# schemat2.net
KiCad netlist of a schematic drawn in EAGLE
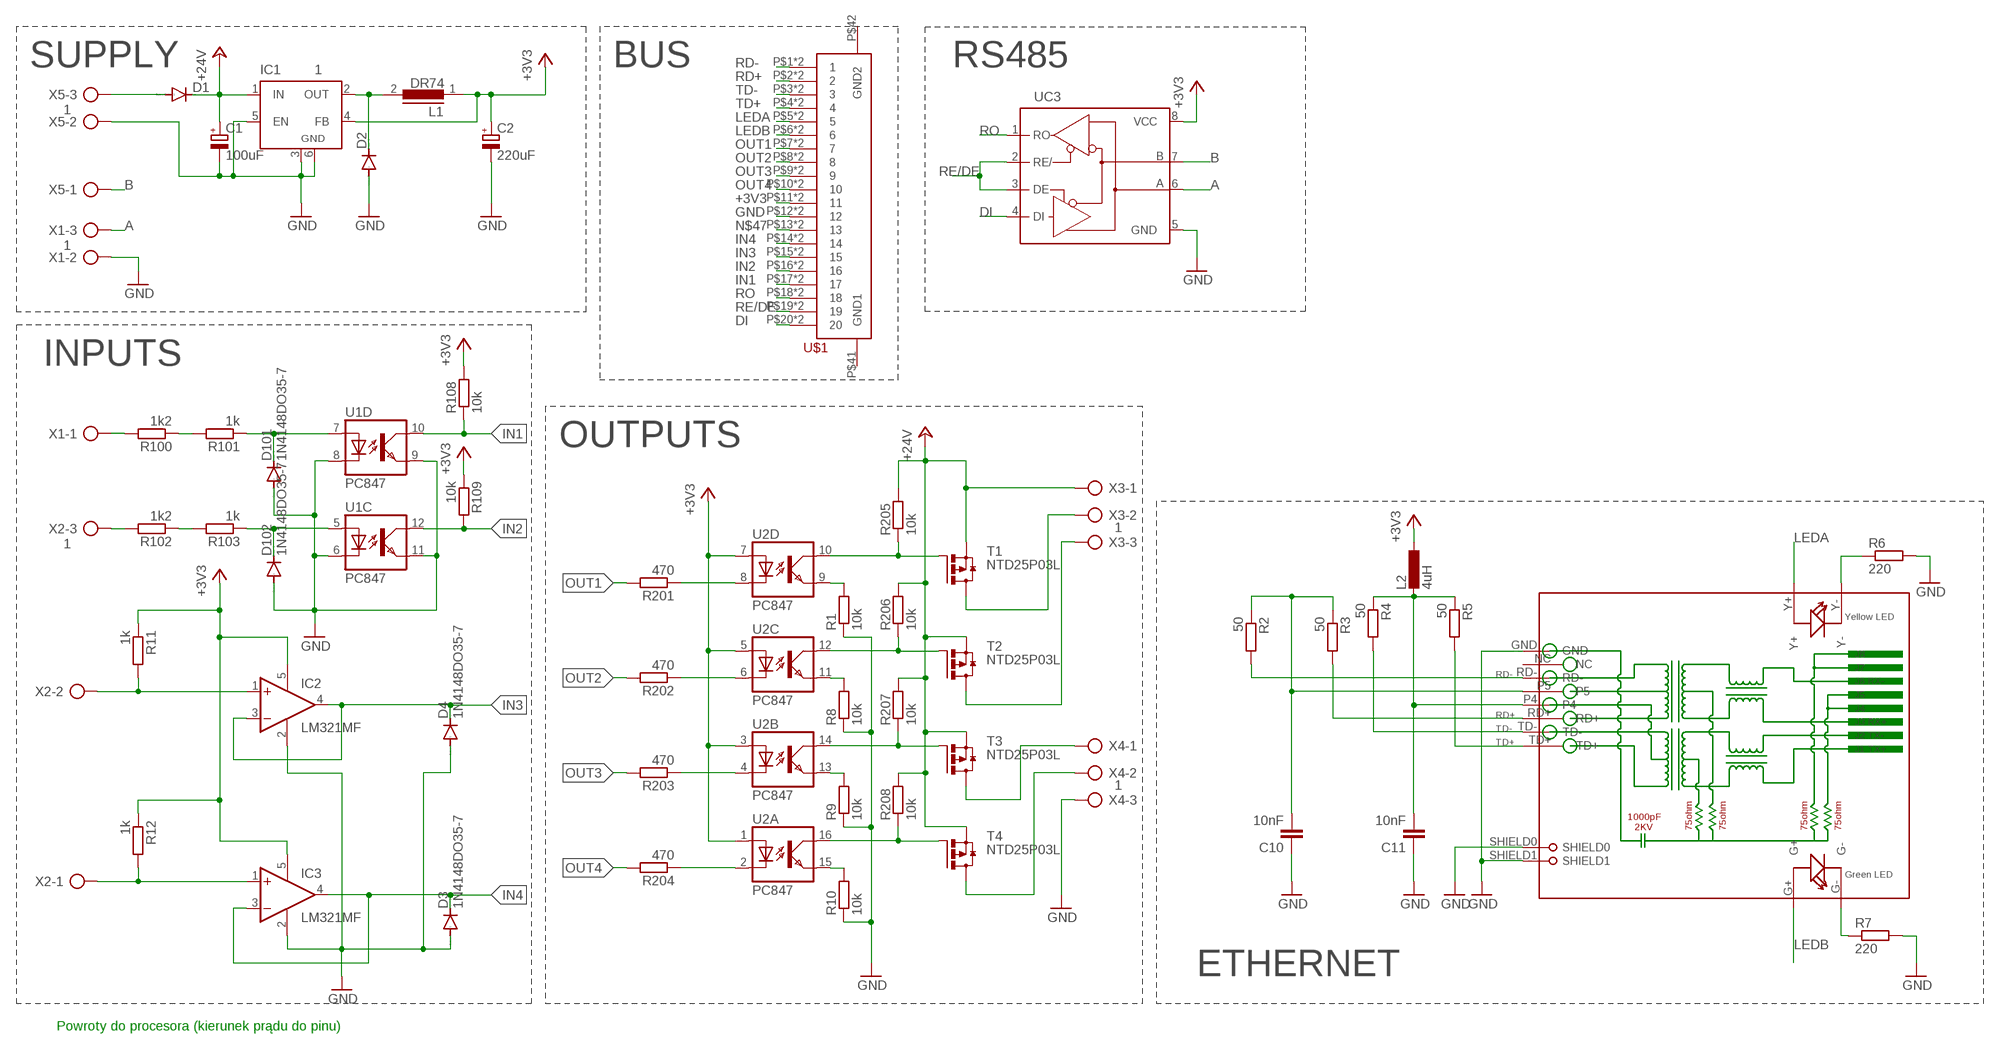
[diagram p0: schematic, sheet 1]

(export (version "E")
  (design (tool "Eeschema 10.0.6"))
  (components
    (comp (ref "C1")
      (value "100uF")
      (footprint "eagle-import:SANYO-OSCON_SMD_E7")
      (libsource (lib "eagle-import") (part "CPOL-EUSANYO_SMD_E7"))
    )
    (comp (ref "C2")
      (value "220uF")
      (footprint "eagle-import:SANYO-OSCON_SMD_E7")
      (libsource (lib "eagle-import") (part "CPOL-EUSANYO_SMD_E7"))
    )
    (comp (ref "C10")
      (value "10nF")
      (footprint "eagle-import:C0805")
      (libsource (lib "eagle-import") (part "C-0805"))
    )
    (comp (ref "C11")
      (value "10nF")
      (footprint "eagle-import:C0805")
      (libsource (lib "eagle-import") (part "C-0805"))
    )
    (comp (ref "D1")
      (value "S1M")
      (footprint "eagle-import:SMA")
      (libsource (lib "eagle-import") (part "S1M"))
    )
    (comp (ref "D2")
      (value "S1M")
      (footprint "eagle-import:SMA")
      (libsource (lib "eagle-import") (part "S1M"))
    )
    (comp (ref "D3")
      (value "1N4148DO35-7")
      (footprint "eagle-import:DO35-7")
      (libsource (lib "eagle-import") (part "1N4148DO35-7"))
    )
    (comp (ref "D4")
      (value "1N4148DO35-7")
      (footprint "eagle-import:DO35-7")
      (libsource (lib "eagle-import") (part "1N4148DO35-7"))
    )
    (comp (ref "D101")
      (value "1N4148DO35-7")
      (footprint "eagle-import:DO35-7")
      (libsource (lib "eagle-import") (part "1N4148DO35-7"))
    )
    (comp (ref "D102")
      (value "1N4148DO35-7")
      (footprint "eagle-import:DO35-7")
      (libsource (lib "eagle-import") (part "1N4148DO35-7"))
    )
    (comp (ref "IC1")
      (value "1")
      (footprint "eagle-import:TO263-5")
      (libsource (lib "eagle-import") (part "LM2596S"))
    )
    (comp (ref "IC2")
      (value "LM321MF")
      (footprint "eagle-import:SOT23-5")
      (libsource (lib "eagle-import") (part "LM321?MF"))
    )
    (comp (ref "IC3")
      (value "LM321MF")
      (footprint "eagle-import:SOT23-5")
      (libsource (lib "eagle-import") (part "LM321?MF"))
    )
    (comp (ref "L1")
      (value "DR74")
      (footprint "eagle-import:DR74")
      (libsource (lib "eagle-import") (part "DR74"))
    )
    (comp (ref "L2")
      (value "4uH")
      (footprint "eagle-import:L2012C")
      (libsource (lib "eagle-import") (part "L-EUL2012C"))
    )
    (comp (ref "R1")
      (value "10k")
      (footprint "eagle-import:R0805W")
      (libsource (lib "eagle-import") (part "R-0805W"))
    )
    (comp (ref "R2")
      (value "50")
      (footprint "eagle-import:R0805")
      (libsource (lib "eagle-import") (part "R-0805"))
    )
    (comp (ref "R3")
      (value "50")
      (footprint "eagle-import:R0805")
      (libsource (lib "eagle-import") (part "R-0805"))
    )
    (comp (ref "R4")
      (value "50")
      (footprint "eagle-import:R0805")
      (libsource (lib "eagle-import") (part "R-0805"))
    )
    (comp (ref "R5")
      (value "50")
      (footprint "eagle-import:R0805")
      (libsource (lib "eagle-import") (part "R-0805"))
    )
    (comp (ref "R6")
      (value "220")
      (footprint "eagle-import:R0805")
      (libsource (lib "eagle-import") (part "R-0805"))
    )
    (comp (ref "R7")
      (value "220")
      (footprint "eagle-import:R0805")
      (libsource (lib "eagle-import") (part "R-0805"))
    )
    (comp (ref "R8")
      (value "10k")
      (footprint "eagle-import:R0805W")
      (libsource (lib "eagle-import") (part "R-0805W"))
    )
    (comp (ref "R9")
      (value "10k")
      (footprint "eagle-import:R0805W")
      (libsource (lib "eagle-import") (part "R-0805W"))
    )
    (comp (ref "R10")
      (value "10k")
      (footprint "eagle-import:R0805W")
      (libsource (lib "eagle-import") (part "R-0805W"))
    )
    (comp (ref "R11")
      (value "1k")
      (footprint "eagle-import:R0805")
      (libsource (lib "eagle-import") (part "R-0805"))
    )
    (comp (ref "R12")
      (value "1k")
      (footprint "eagle-import:R0805")
      (libsource (lib "eagle-import") (part "R-0805"))
    )
    (comp (ref "R100")
      (value "1k2")
      (footprint "eagle-import:R0805")
      (libsource (lib "eagle-import") (part "R-0805"))
    )
    (comp (ref "R101")
      (value "1k")
      (footprint "eagle-import:R0805")
      (libsource (lib "eagle-import") (part "R-0805"))
    )
    (comp (ref "R102")
      (value "1k2")
      (footprint "eagle-import:R0805")
      (libsource (lib "eagle-import") (part "R-0805"))
    )
    (comp (ref "R103")
      (value "1k")
      (footprint "eagle-import:R0805")
      (libsource (lib "eagle-import") (part "R-0805"))
    )
    (comp (ref "R108")
      (value "10k")
      (footprint "eagle-import:R0805")
      (libsource (lib "eagle-import") (part "R-0805"))
    )
    (comp (ref "R109")
      (value "10k")
      (footprint "eagle-import:R0805")
      (libsource (lib "eagle-import") (part "R-0805"))
    )
    (comp (ref "R201")
      (value "470")
      (footprint "eagle-import:R0805")
      (libsource (lib "eagle-import") (part "R-0805"))
    )
    (comp (ref "R202")
      (value "470")
      (footprint "eagle-import:R0805")
      (libsource (lib "eagle-import") (part "R-0805"))
    )
    (comp (ref "R203")
      (value "470")
      (footprint "eagle-import:R0805")
      (libsource (lib "eagle-import") (part "R-0805"))
    )
    (comp (ref "R204")
      (value "470")
      (footprint "eagle-import:R0805")
      (libsource (lib "eagle-import") (part "R-0805"))
    )
    (comp (ref "R205")
      (value "10k")
      (footprint "eagle-import:R0805W")
      (libsource (lib "eagle-import") (part "R-0805W"))
    )
    (comp (ref "R206")
      (value "10k")
      (footprint "eagle-import:R0805W")
      (libsource (lib "eagle-import") (part "R-0805W"))
    )
    (comp (ref "R207")
      (value "10k")
      (footprint "eagle-import:R0805W")
      (libsource (lib "eagle-import") (part "R-0805W"))
    )
    (comp (ref "R208")
      (value "10k")
      (footprint "eagle-import:R0805W")
      (libsource (lib "eagle-import") (part "R-0805W"))
    )
    (comp (ref "RJ1")
      (value "HR911105A")
      (footprint "eagle-import:HR911105A")
      (libsource (lib "eagle-import") (part "HR911105A"))
    )
    (comp (ref "T1")
      (value "NTD25P03L")
      (footprint "eagle-import:DPACK")
      (libsource (lib "eagle-import") (part "NTD25P03L"))
    )
    (comp (ref "T2")
      (value "NTD25P03L")
      (footprint "eagle-import:DPACK")
      (libsource (lib "eagle-import") (part "NTD25P03L"))
    )
    (comp (ref "T3")
      (value "NTD25P03L")
      (footprint "eagle-import:DPACK")
      (libsource (lib "eagle-import") (part "NTD25P03L"))
    )
    (comp (ref "T4")
      (value "NTD25P03L")
      (footprint "eagle-import:DPACK")
      (libsource (lib "eagle-import") (part "NTD25P03L"))
    )
    (comp (ref "U$1")
      (value "FFC(FPC)_ZIF_20_PINV")
      (footprint "eagle-import:PCA-2C-20-V-3")
      (libsource (lib "eagle-import") (part "FFC(FPC)_ZIF_20_PINV"))
    )
    (comp (ref "U1")
      (value "PC847")
      (footprint "eagle-import:SO16")
      (libsource (lib "eagle-import") (part "PC847"))
    )
    (comp (ref "U2")
      (value "PC847")
      (footprint "eagle-import:SO16")
      (libsource (lib "eagle-import") (part "PC847"))
    )
    (comp (ref "UC3")
      (value "MAX3468CSA")
      (footprint "eagle-import:SO08")
      (fields (field (name "MPN") "MAX3468CSA+"))
      (libsource (lib "eagle-import") (part "MAX34SA68C"))
    )
    (comp (ref "X1")
      (value "1")
      (footprint "eagle-import:AK500_3")
      (libsource (lib "eagle-import") (part "AK500/3"))
    )
    (comp (ref "X2")
      (value "1")
      (footprint "eagle-import:AK500_3")
      (libsource (lib "eagle-import") (part "AK500/3"))
    )
    (comp (ref "X3")
      (value "1")
      (footprint "eagle-import:AK500_3")
      (libsource (lib "eagle-import") (part "AK500/3"))
    )
    (comp (ref "X4")
      (value "1")
      (footprint "eagle-import:AK500_3")
      (libsource (lib "eagle-import") (part "AK500/3"))
    )
    (comp (ref "X5")
      (value "1")
      (footprint "eagle-import:AK500_3")
      (libsource (lib "eagle-import") (part "AK500/3"))
    )
  )
  (nets
    (net (code "1") (name "+3V3") (class "Default")
      (node (ref "C2") (pin "+") (pinfunction "+_+") (pintype "passive"))
      (node (ref "IC1") (pin "4") (pinfunction "FB_4") (pintype "input"))
      (node (ref "IC2") (pin "5") (pinfunction "V+_5") (pintype "power_in"))
      (node (ref "IC3") (pin "5") (pinfunction "V+_5") (pintype "power_in"))
      (node (ref "L1") (pin "1") (pinfunction "1_1") (pintype "passive"))
      (node (ref "L2") (pin "1") (pinfunction "1_1") (pintype "passive"))
      (node (ref "R108") (pin "2") (pinfunction "2_2") (pintype "passive"))
      (node (ref "R109") (pin "1") (pinfunction "1_1") (pintype "passive"))
      (node (ref "R11") (pin "1") (pinfunction "1_1") (pintype "passive"))
      (node (ref "R12") (pin "1") (pinfunction "1_1") (pintype "passive"))
      (node (ref "U$1") (pin "P$11") (pinfunction "11_P$11") (pintype "bidirectional"))
      (node (ref "U$1") (pin "P$31") (pinfunction "11_P$31") (pintype "bidirectional"))
      (node (ref "U2") (pin "1") (pinfunction "A_1") (pintype "passive"))
      (node (ref "U2") (pin "3") (pinfunction "A_3") (pintype "passive"))
      (node (ref "U2") (pin "5") (pinfunction "A_5") (pintype "passive"))
      (node (ref "U2") (pin "7") (pinfunction "A_7") (pintype "passive"))
      (node (ref "UC3") (pin "8") (pinfunction "VCC_8") (pintype "power_in"))
    )
    (net (code "2") (name "+24V") (class "Default")
      (node (ref "C1") (pin "+") (pinfunction "+_+") (pintype "passive"))
      (node (ref "D1") (pin "C") (pinfunction "C_C") (pintype "passive"))
      (node (ref "IC1") (pin "1") (pinfunction "IN_1") (pintype "input"))
      (node (ref "R205") (pin "2") (pinfunction "2_2") (pintype "passive"))
      (node (ref "R206") (pin "2") (pinfunction "2_2") (pintype "passive"))
      (node (ref "R207") (pin "2") (pinfunction "2_2") (pintype "passive"))
      (node (ref "R208") (pin "2") (pinfunction "2_2") (pintype "passive"))
      (node (ref "T1") (pin "3") (pinfunction "S_3") (pintype "passive"))
      (node (ref "T2") (pin "3") (pinfunction "S_3") (pintype "passive"))
      (node (ref "T3") (pin "3") (pinfunction "S_3") (pintype "passive"))
      (node (ref "T4") (pin "3") (pinfunction "S_3") (pintype "passive"))
      (node (ref "X3") (pin "1") (pinfunction "KL_1") (pintype "passive"))
    )
    (net (code "3") (name "/A") (class "Default")
      (node (ref "UC3") (pin "6") (pinfunction "A_6") (pintype "passive"))
      (node (ref "X1") (pin "3") (pinfunction "KL_3") (pintype "passive"))
    )
    (net (code "4") (name "/B") (class "Default")
      (node (ref "UC3") (pin "7") (pinfunction "B_7") (pintype "passive"))
      (node (ref "X5") (pin "1") (pinfunction "KL_1") (pintype "passive"))
    )
    (net (code "5") (name "/DI") (class "Default")
      (node (ref "U$1") (pin "P$20") (pinfunction "20_P$20") (pintype "bidirectional"))
      (node (ref "U$1") (pin "P$40") (pinfunction "20_P$40") (pintype "bidirectional"))
      (node (ref "UC3") (pin "4") (pinfunction "DI_4") (pintype "input"))
    )
    (net (code "6") (name "/LEDA") (class "Default")
      (node (ref "RJ1") (pin "Y+") (pinfunction "Y+_Y+") (pintype "bidirectional"))
      (node (ref "U$1") (pin "P$25") (pinfunction "5_P$25") (pintype "bidirectional"))
      (node (ref "U$1") (pin "P$5") (pinfunction "5_P$5") (pintype "bidirectional"))
    )
    (net (code "7") (name "/LEDB") (class "Default")
      (node (ref "RJ1") (pin "G+") (pinfunction "G+_G+") (pintype "bidirectional"))
      (node (ref "U$1") (pin "P$26") (pinfunction "6_P$26") (pintype "bidirectional"))
      (node (ref "U$1") (pin "P$6") (pinfunction "6_P$6") (pintype "bidirectional"))
    )
    (net (code "8") (name "/N$47") (class "Default")
      (node (ref "U$1") (pin "P$13") (pinfunction "13_P$13") (pintype "bidirectional"))
      (node (ref "U$1") (pin "P$33") (pinfunction "13_P$33") (pintype "bidirectional"))
    )
    (net (code "9") (name "/RD+") (class "Default")
      (node (ref "R3") (pin "2") (pinfunction "2_2") (pintype "passive"))
      (node (ref "RJ1") (pin "RD+") (pinfunction "RD+_RD+") (pintype "bidirectional"))
      (node (ref "U$1") (pin "P$2") (pinfunction "2_P$2") (pintype "bidirectional"))
      (node (ref "U$1") (pin "P$22") (pinfunction "2_P$22") (pintype "bidirectional"))
    )
    (net (code "10") (name "/RD-") (class "Default")
      (node (ref "R2") (pin "2") (pinfunction "2_2") (pintype "passive"))
      (node (ref "RJ1") (pin "RD-") (pinfunction "RD-_RD-") (pintype "bidirectional"))
      (node (ref "U$1") (pin "P$1") (pinfunction "1_P$1") (pintype "bidirectional"))
      (node (ref "U$1") (pin "P$21") (pinfunction "1_P$21") (pintype "bidirectional"))
    )
    (net (code "11") (name "/RE{slash}DE") (class "Default")
      (node (ref "U$1") (pin "P$19") (pinfunction "19_P$19") (pintype "bidirectional"))
      (node (ref "U$1") (pin "P$39") (pinfunction "19_P$39") (pintype "bidirectional"))
      (node (ref "UC3") (pin "2") (pinfunction "RE/_2") (pintype "input"))
      (node (ref "UC3") (pin "3") (pinfunction "DE_3") (pintype "input"))
    )
    (net (code "12") (name "/RO") (class "Default")
      (node (ref "U$1") (pin "P$18") (pinfunction "18_P$18") (pintype "bidirectional"))
      (node (ref "U$1") (pin "P$38") (pinfunction "18_P$38") (pintype "bidirectional"))
      (node (ref "UC3") (pin "1") (pinfunction "RO_1") (pintype "output"))
    )
    (net (code "13") (name "/TD+") (class "Default")
      (node (ref "R5") (pin "2") (pinfunction "2_2") (pintype "passive"))
      (node (ref "RJ1") (pin "TD+") (pinfunction "TD+_TD+") (pintype "bidirectional"))
      (node (ref "U$1") (pin "P$24") (pinfunction "4_P$24") (pintype "bidirectional"))
      (node (ref "U$1") (pin "P$4") (pinfunction "4_P$4") (pintype "bidirectional"))
    )
    (net (code "14") (name "/TD-") (class "Default")
      (node (ref "R4") (pin "2") (pinfunction "2_2") (pintype "passive"))
      (node (ref "RJ1") (pin "TD-") (pinfunction "TD-_TD-") (pintype "bidirectional"))
      (node (ref "U$1") (pin "P$23") (pinfunction "3_P$23") (pintype "bidirectional"))
      (node (ref "U$1") (pin "P$3") (pinfunction "3_P$3") (pintype "bidirectional"))
    )
    (net (code "15") (name "GND") (class "Default")
      (node (ref "C1") (pin "-") (pinfunction "-_-") (pintype "passive"))
      (node (ref "C10") (pin "1") (pinfunction "1_1") (pintype "passive"))
      (node (ref "C11") (pin "1") (pinfunction "1_1") (pintype "passive"))
      (node (ref "C2") (pin "-") (pinfunction "-_-") (pintype "passive"))
      (node (ref "D101") (pin "A") (pinfunction "A_A") (pintype "passive"))
      (node (ref "D102") (pin "A") (pinfunction "A_A") (pintype "passive"))
      (node (ref "D2") (pin "A") (pinfunction "A_A") (pintype "passive"))
      (node (ref "D3") (pin "A") (pinfunction "A_A") (pintype "passive"))
      (node (ref "D4") (pin "A") (pinfunction "A_A") (pintype "passive"))
      (node (ref "IC1") (pin "3") (pinfunction "GND_3") (pintype "power_in"))
      (node (ref "IC1") (pin "5") (pinfunction "EN_5") (pintype "input"))
      (node (ref "IC1") (pin "6") (pinfunction "GND_6") (pintype "power_in"))
      (node (ref "IC2") (pin "2") (pinfunction "V-_2") (pintype "power_in"))
      (node (ref "IC3") (pin "2") (pinfunction "V-_2") (pintype "power_in"))
      (node (ref "R1") (pin "1") (pinfunction "1_1") (pintype "passive"))
      (node (ref "R10") (pin "1") (pinfunction "1_1") (pintype "passive"))
      (node (ref "R6") (pin "2") (pinfunction "2_2") (pintype "passive"))
      (node (ref "R7") (pin "2") (pinfunction "2_2") (pintype "passive"))
      (node (ref "R8") (pin "1") (pinfunction "1_1") (pintype "passive"))
      (node (ref "R9") (pin "1") (pinfunction "1_1") (pintype "passive"))
      (node (ref "RJ1") (pin "GND") (pinfunction "GND_GND") (pintype "bidirectional"))
      (node (ref "RJ1") (pin "SHIELD0") (pinfunction "SHIELD0_SHIELD0") (pintype "bidirectional"))
      (node (ref "RJ1") (pin "SHIELD1") (pinfunction "SHIELD1_SHIELD1") (pintype "bidirectional"))
      (node (ref "U$1") (pin "P$12") (pinfunction "12_P$12") (pintype "bidirectional"))
      (node (ref "U$1") (pin "P$32") (pinfunction "12_P$32") (pintype "bidirectional"))
      (node (ref "U1") (pin "11") (pinfunction "EMIT_11") (pintype "passive"))
      (node (ref "U1") (pin "6") (pinfunction "C_6") (pintype "passive"))
      (node (ref "U1") (pin "8") (pinfunction "C_8") (pintype "passive"))
      (node (ref "U1") (pin "9") (pinfunction "EMIT_9") (pintype "passive"))
      (node (ref "UC3") (pin "5") (pinfunction "GND_5") (pintype "power_in"))
      (node (ref "X1") (pin "2") (pinfunction "KL_2") (pintype "passive"))
      (node (ref "X4") (pin "3") (pinfunction "KL_3") (pintype "passive"))
      (node (ref "X5") (pin "2") (pinfunction "KL_2") (pintype "passive"))
    )
    (net (code "16") (name "IN1") (class "Default")
      (node (ref "R108") (pin "1") (pinfunction "1_1") (pintype "passive"))
      (node (ref "U$1") (pin "P$17") (pinfunction "17_P$17") (pintype "bidirectional"))
      (node (ref "U$1") (pin "P$37") (pinfunction "17_P$37") (pintype "bidirectional"))
      (node (ref "U1") (pin "10") (pinfunction "COL_10") (pintype "passive"))
    )
    (net (code "17") (name "IN2") (class "Default")
      (node (ref "R109") (pin "2") (pinfunction "2_2") (pintype "passive"))
      (node (ref "U$1") (pin "P$16") (pinfunction "16_P$16") (pintype "bidirectional"))
      (node (ref "U$1") (pin "P$36") (pinfunction "16_P$36") (pintype "bidirectional"))
      (node (ref "U1") (pin "12") (pinfunction "COL_12") (pintype "passive"))
    )
    (net (code "18") (name "IN3") (class "Default")
      (node (ref "D4") (pin "C") (pinfunction "C_C") (pintype "passive"))
      (node (ref "IC2") (pin "3") (pinfunction "-IN_3") (pintype "input"))
      (node (ref "IC2") (pin "4") (pinfunction "OUT_4") (pintype "output"))
      (node (ref "U$1") (pin "P$15") (pinfunction "15_P$15") (pintype "bidirectional"))
      (node (ref "U$1") (pin "P$35") (pinfunction "15_P$35") (pintype "bidirectional"))
    )
    (net (code "19") (name "IN4") (class "Default")
      (node (ref "D3") (pin "C") (pinfunction "C_C") (pintype "passive"))
      (node (ref "IC3") (pin "3") (pinfunction "-IN_3") (pintype "input"))
      (node (ref "IC3") (pin "4") (pinfunction "OUT_4") (pintype "output"))
      (node (ref "U$1") (pin "P$14") (pinfunction "14_P$14") (pintype "bidirectional"))
      (node (ref "U$1") (pin "P$34") (pinfunction "14_P$34") (pintype "bidirectional"))
    )
    (net (code "20") (name "Net-(C10-Pad2)") (class "Default")
      (node (ref "C10") (pin "2") (pinfunction "2_2") (pintype "passive"))
      (node (ref "R2") (pin "1") (pinfunction "1_1") (pintype "passive"))
      (node (ref "R3") (pin "1") (pinfunction "1_1") (pintype "passive"))
      (node (ref "RJ1") (pin "P5") (pinfunction "P5_P5") (pintype "bidirectional"))
    )
    (net (code "21") (name "Net-(C11-Pad2)") (class "Default")
      (node (ref "C11") (pin "2") (pinfunction "2_2") (pintype "passive"))
      (node (ref "L2") (pin "2") (pinfunction "2_2") (pintype "passive"))
      (node (ref "R4") (pin "1") (pinfunction "1_1") (pintype "passive"))
      (node (ref "R5") (pin "1") (pinfunction "1_1") (pintype "passive"))
      (node (ref "RJ1") (pin "P4") (pinfunction "P4_P4") (pintype "bidirectional"))
    )
    (net (code "22") (name "Net-(IC1-OUT)") (class "Default")
      (node (ref "D2") (pin "C") (pinfunction "C_C") (pintype "passive"))
      (node (ref "IC1") (pin "2") (pinfunction "OUT_2") (pintype "output"))
      (node (ref "L1") (pin "2") (pinfunction "2_2") (pintype "passive"))
    )
    (net (code "23") (name "Net-(IC2-+IN)") (class "Default")
      (node (ref "IC2") (pin "1") (pinfunction "+IN_1") (pintype "input"))
      (node (ref "R11") (pin "2") (pinfunction "2_2") (pintype "passive"))
      (node (ref "X2") (pin "2") (pinfunction "KL_2") (pintype "passive"))
    )
    (net (code "24") (name "Net-(IC3-+IN)") (class "Default")
      (node (ref "IC3") (pin "1") (pinfunction "+IN_1") (pintype "input"))
      (node (ref "R12") (pin "2") (pinfunction "2_2") (pintype "passive"))
      (node (ref "X2") (pin "1") (pinfunction "KL_1") (pintype "passive"))
    )
    (net (code "25") (name "Net-(R6-Pad1)") (class "Default")
      (node (ref "R6") (pin "1") (pinfunction "1_1") (pintype "passive"))
      (node (ref "RJ1") (pin "Y-") (pinfunction "Y-_Y-") (pintype "bidirectional"))
    )
    (net (code "26") (name "Net-(R7-Pad1)") (class "Default")
      (node (ref "R7") (pin "1") (pinfunction "1_1") (pintype "passive"))
      (node (ref "RJ1") (pin "G-") (pinfunction "G-_G-") (pintype "bidirectional"))
    )
    (net (code "27") (name "Net-(R100-Pad1)") (class "Default")
      (node (ref "R100") (pin "1") (pinfunction "1_1") (pintype "passive"))
      (node (ref "R101") (pin "2") (pinfunction "2_2") (pintype "passive"))
    )
    (net (code "28") (name "Net-(R102-Pad1)") (class "Default")
      (node (ref "R102") (pin "1") (pinfunction "1_1") (pintype "passive"))
      (node (ref "R103") (pin "2") (pinfunction "2_2") (pintype "passive"))
    )
    (net (code "29") (name "Net-(T1-D)") (class "Default")
      (node (ref "T1") (pin "2") (pinfunction "D_2") (pintype "passive"))
      (node (ref "X3") (pin "2") (pinfunction "KL_2") (pintype "passive"))
    )
    (net (code "30") (name "Net-(T1-G)") (class "Default")
      (node (ref "R205") (pin "1") (pinfunction "1_1") (pintype "passive"))
      (node (ref "T1") (pin "1") (pinfunction "G_1") (pintype "passive"))
      (node (ref "U2") (pin "10") (pinfunction "COL_10") (pintype "passive"))
    )
    (net (code "31") (name "Net-(T2-D)") (class "Default")
      (node (ref "T2") (pin "2") (pinfunction "D_2") (pintype "passive"))
      (node (ref "X3") (pin "3") (pinfunction "KL_3") (pintype "passive"))
    )
    (net (code "32") (name "Net-(T2-G)") (class "Default")
      (node (ref "R206") (pin "1") (pinfunction "1_1") (pintype "passive"))
      (node (ref "T2") (pin "1") (pinfunction "G_1") (pintype "passive"))
      (node (ref "U2") (pin "12") (pinfunction "COL_12") (pintype "passive"))
    )
    (net (code "33") (name "Net-(T3-D)") (class "Default")
      (node (ref "T3") (pin "2") (pinfunction "D_2") (pintype "passive"))
      (node (ref "X4") (pin "1") (pinfunction "KL_1") (pintype "passive"))
    )
    (net (code "34") (name "Net-(T3-G)") (class "Default")
      (node (ref "R207") (pin "1") (pinfunction "1_1") (pintype "passive"))
      (node (ref "T3") (pin "1") (pinfunction "G_1") (pintype "passive"))
      (node (ref "U2") (pin "14") (pinfunction "COL_14") (pintype "passive"))
    )
    (net (code "35") (name "Net-(T4-D)") (class "Default")
      (node (ref "T4") (pin "2") (pinfunction "D_2") (pintype "passive"))
      (node (ref "X4") (pin "2") (pinfunction "KL_2") (pintype "passive"))
    )
    (net (code "36") (name "Net-(T4-G)") (class "Default")
      (node (ref "R208") (pin "1") (pinfunction "1_1") (pintype "passive"))
      (node (ref "T4") (pin "1") (pinfunction "G_1") (pintype "passive"))
      (node (ref "U2") (pin "16") (pinfunction "COL_16") (pintype "passive"))
    )
    (net (code "37") (name "Net-(U1C-A)") (class "Default")
      (node (ref "D102") (pin "C") (pinfunction "C_C") (pintype "passive"))
      (node (ref "R103") (pin "1") (pinfunction "1_1") (pintype "passive"))
      (node (ref "U1") (pin "5") (pinfunction "A_5") (pintype "passive"))
    )
    (net (code "38") (name "Net-(U1D-A)") (class "Default")
      (node (ref "D101") (pin "C") (pinfunction "C_C") (pintype "passive"))
      (node (ref "R101") (pin "1") (pinfunction "1_1") (pintype "passive"))
      (node (ref "U1") (pin "7") (pinfunction "A_7") (pintype "passive"))
    )
    (net (code "39") (name "Net-(U2A-C)") (class "Default")
      (node (ref "R204") (pin "1") (pinfunction "1_1") (pintype "passive"))
      (node (ref "U2") (pin "2") (pinfunction "C_2") (pintype "passive"))
    )
    (net (code "40") (name "Net-(U2A-EMIT)") (class "Default")
      (node (ref "R10") (pin "2") (pinfunction "2_2") (pintype "passive"))
      (node (ref "U2") (pin "15") (pinfunction "EMIT_15") (pintype "passive"))
    )
    (net (code "41") (name "Net-(U2B-C)") (class "Default")
      (node (ref "R203") (pin "1") (pinfunction "1_1") (pintype "passive"))
      (node (ref "U2") (pin "4") (pinfunction "C_4") (pintype "passive"))
    )
    (net (code "42") (name "Net-(U2B-EMIT)") (class "Default")
      (node (ref "R9") (pin "2") (pinfunction "2_2") (pintype "passive"))
      (node (ref "U2") (pin "13") (pinfunction "EMIT_13") (pintype "passive"))
    )
    (net (code "43") (name "Net-(U2C-C)") (class "Default")
      (node (ref "R202") (pin "1") (pinfunction "1_1") (pintype "passive"))
      (node (ref "U2") (pin "6") (pinfunction "C_6") (pintype "passive"))
    )
    (net (code "44") (name "Net-(U2C-EMIT)") (class "Default")
      (node (ref "R8") (pin "2") (pinfunction "2_2") (pintype "passive"))
      (node (ref "U2") (pin "11") (pinfunction "EMIT_11") (pintype "passive"))
    )
    (net (code "45") (name "Net-(U2D-C)") (class "Default")
      (node (ref "R201") (pin "1") (pinfunction "1_1") (pintype "passive"))
      (node (ref "U2") (pin "8") (pinfunction "C_8") (pintype "passive"))
    )
    (net (code "46") (name "Net-(U2D-EMIT)") (class "Default")
      (node (ref "R1") (pin "2") (pinfunction "2_2") (pintype "passive"))
      (node (ref "U2") (pin "9") (pinfunction "EMIT_9") (pintype "passive"))
    )
    (net (code "47") (name "Net-(X1A-KL)") (class "Default")
      (node (ref "R100") (pin "2") (pinfunction "2_2") (pintype "passive"))
      (node (ref "X1") (pin "1") (pinfunction "KL_1") (pintype "passive"))
    )
    (net (code "48") (name "Net-(X2C-KL)") (class "Default")
      (node (ref "R102") (pin "2") (pinfunction "2_2") (pintype "passive"))
      (node (ref "X2") (pin "3") (pinfunction "KL_3") (pintype "passive"))
    )
    (net (code "49") (name "Net-(X5C-KL)") (class "Default")
      (node (ref "D1") (pin "A") (pinfunction "A_A") (pintype "passive"))
      (node (ref "X5") (pin "3") (pinfunction "KL_3") (pintype "passive"))
    )
    (net (code "50") (name "OUT1") (class "Default")
      (node (ref "R201") (pin "2") (pinfunction "2_2") (pintype "passive"))
      (node (ref "U$1") (pin "P$27") (pinfunction "7_P$27") (pintype "bidirectional"))
      (node (ref "U$1") (pin "P$7") (pinfunction "7_P$7") (pintype "bidirectional"))
    )
    (net (code "51") (name "OUT2") (class "Default")
      (node (ref "R202") (pin "2") (pinfunction "2_2") (pintype "passive"))
      (node (ref "U$1") (pin "P$28") (pinfunction "8_P$28") (pintype "bidirectional"))
      (node (ref "U$1") (pin "P$8") (pinfunction "8_P$8") (pintype "bidirectional"))
    )
    (net (code "52") (name "OUT3") (class "Default")
      (node (ref "R203") (pin "2") (pinfunction "2_2") (pintype "passive"))
      (node (ref "U$1") (pin "P$29") (pinfunction "9_P$29") (pintype "bidirectional"))
      (node (ref "U$1") (pin "P$9") (pinfunction "9_P$9") (pintype "bidirectional"))
    )
    (net (code "53") (name "OUT4") (class "Default")
      (node (ref "R204") (pin "2") (pinfunction "2_2") (pintype "passive"))
      (node (ref "U$1") (pin "P$10") (pinfunction "10_P$10") (pintype "bidirectional"))
      (node (ref "U$1") (pin "P$30") (pinfunction "10_P$30") (pintype "bidirectional"))
    )
    (net (code "54") (name "unconnected-(RJ1-PadNC)") (class "Default")
      (node (ref "RJ1") (pin "NC") (pinfunction "NC_NC") (pintype "bidirectional"))
    )
    (net (code "55") (name "unconnected-(U$1-GND1-PadP$41)") (class "Default")
      (node (ref "U$1") (pin "P$41") (pinfunction "GND1_P$41") (pintype "bidirectional"))
    )
    (net (code "56") (name "unconnected-(U$1-GND2-PadP$42)") (class "Default")
      (node (ref "U$1") (pin "P$42") (pinfunction "GND2_P$42") (pintype "bidirectional"))
    )
  )
)
